# controller.net
KiCad netlist of a schematic drawn in EAGLE
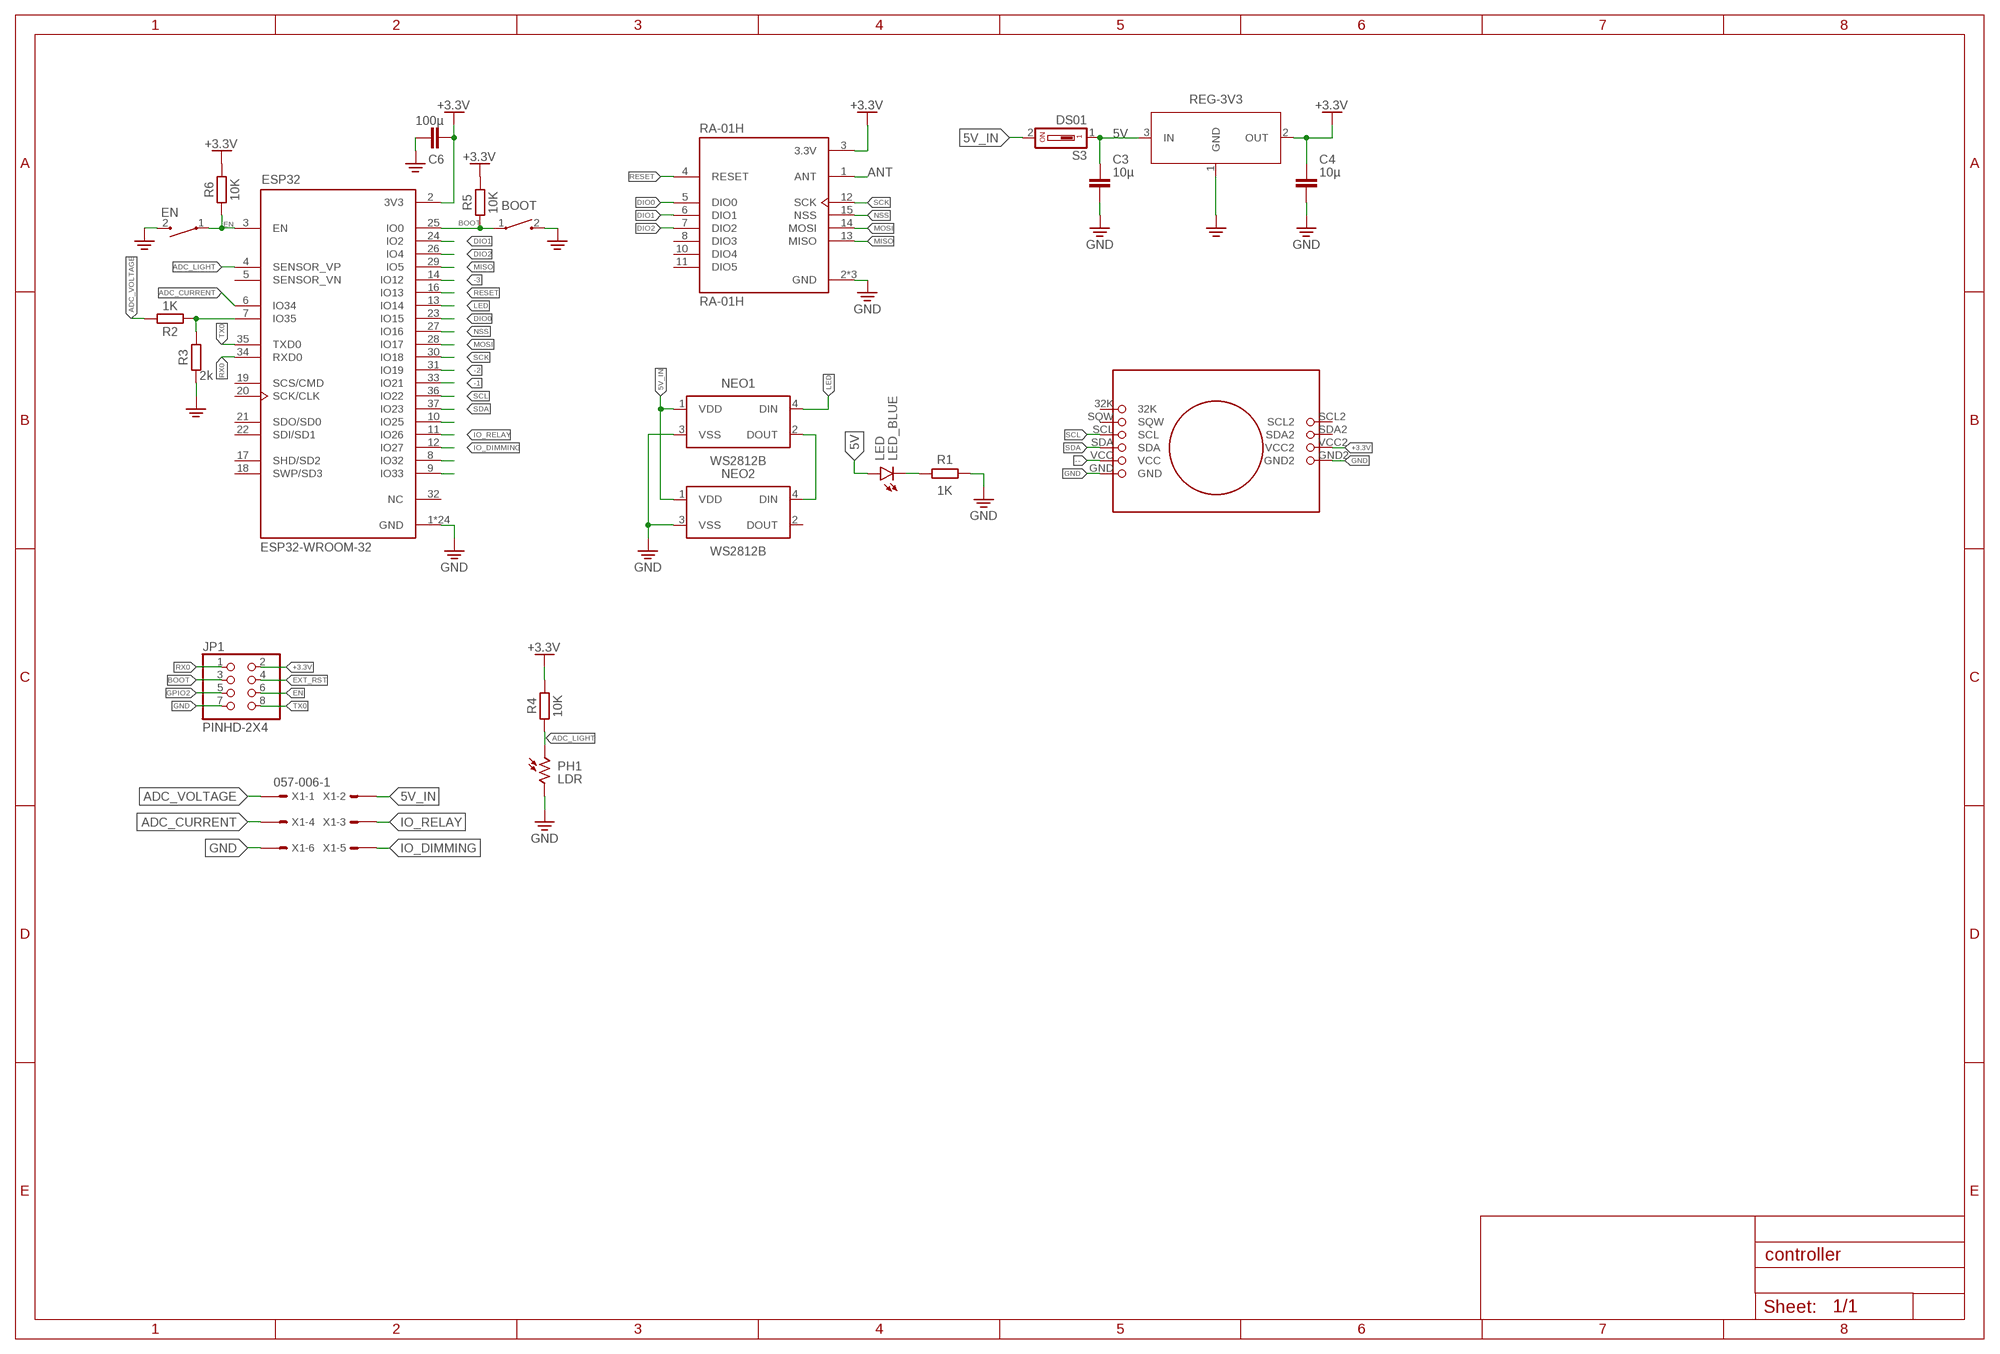
[diagram p0: schematic, sheet 1]

(export (version "E")
  (design (tool "Eeschema 10.0.6"))
  (components
    (comp (ref "BOOT")
      (value "SWITCH")
      (footprint "eagle-import:SW_1437566-3")
      (fields (field (name "MANUFACTURER") "TE CONNECTIVITY"))
      (libsource (lib "eagle-import") (part "SWITCH"))
    )
    (comp (ref "C3")
      (value "10µ")
      (footprint "eagle-import:CAPC2012X110")
      (libsource (lib "eagle-import") (part "CCHIP-0805(2012-METRIC)_"))
    )
    (comp (ref "C4")
      (value "10µ")
      (footprint "eagle-import:CAPC2012X110")
      (libsource (lib "eagle-import") (part "CCHIP-0805(2012-METRIC)_"))
    )
    (comp (ref "C6")
      (value "100µ")
      (footprint "eagle-import:CAPM6032X280")
      (libsource (lib "eagle-import") (part "CTANTALUM-2412(6032-METRIC)_"))
    )
    (comp (ref "EN")
      (value "SWITCH")
      (footprint "eagle-import:SW_1437566-3")
      (fields (field (name "MANUFACTURER") "TE CONNECTIVITY"))
      (libsource (lib "eagle-import") (part "SWITCH"))
    )
    (comp (ref "ESP32")
      (value "ESP32-WROOM-32")
      (footprint "eagle-import:MODULE_ESP32-WROOM-32")
      (fields (field (name "MANUFACTURER") "Espressif Systems"))
      (libsource (lib "eagle-import") (part "ESP32-WROOM-32"))
    )
    (comp (ref "JP1")
      (value "PINHD-2X4")
      (footprint "eagle-import:2X04")
      (libsource (lib "eagle-import") (part "PINHD-2X4"))
    )
    (comp (ref "LED")
      (value "LED_BLUE")
      (footprint "eagle-import:LEDC2012X110N_FLAT-B")
      (libsource (lib "eagle-import") (part "CHIP-FLAT-B_0805"))
    )
    (comp (ref "NEO1")
      (value "WS2812B")
      (footprint "eagle-import:WS2812B")
      (fields (field (name "MANUFACTURER") "Worldsemi"))
      (libsource (lib "eagle-import") (part "WS2812B"))
    )
    (comp (ref "NEO2")
      (value "WS2812B")
      (footprint "eagle-import:WS2812B")
      (fields (field (name "MANUFACTURER") "Worldsemi"))
      (libsource (lib "eagle-import") (part "WS2812B"))
    )
    (comp (ref "PH1")
      (value "LDR")
      (footprint "eagle-import:T0-46-A10XX")
      (libsource (lib "eagle-import") (part "A1050_09"))
    )
    (comp (ref "R1")
      (value "1K")
      (footprint "eagle-import:RESC2012X65")
      (libsource (lib "eagle-import") (part "RCHIP-0805(2012-METRIC)_"))
    )
    (comp (ref "R2")
      (value "1K")
      (footprint "eagle-import:RESC2012X65")
      (libsource (lib "eagle-import") (part "RCHIP-0805(2012-METRIC)_"))
    )
    (comp (ref "R3")
      (value "2k")
      (footprint "eagle-import:RESC2012X65")
      (libsource (lib "eagle-import") (part "RCHIP-0805(2012-METRIC)_"))
    )
    (comp (ref "R4")
      (value "10K")
      (footprint "eagle-import:RESC1608X60")
      (libsource (lib "eagle-import") (part "RCHIP-0603(1608-METRIC)_"))
    )
    (comp (ref "R5")
      (value "10K")
      (footprint "eagle-import:RESC2012X65")
      (libsource (lib "eagle-import") (part "RCHIP-0805(2012-METRIC)_"))
    )
    (comp (ref "R6")
      (value "10K")
      (footprint "eagle-import:RESC2012X65")
      (libsource (lib "eagle-import") (part "RCHIP-0805(2012-METRIC)_"))
    )
    (comp (ref "RA-01H")
      (value "RA-01H")
      (footprint "eagle-import:RA-01H")
      (fields (field (name "MANUFACTURER") "AI-Thinker"))
      (libsource (lib "eagle-import") (part "RA-01H"))
    )
    (comp (ref "REG-3V3")
      (value "NCP1117ST33T3G")
      (footprint "eagle-import:SOT230P700X170-4")
      (fields (field (name "MANUFACTURER") "ON Semiconductor"))
      (libsource (lib "eagle-import") (part "NCP1117ST33T3GSOT-223"))
    )
    (comp (ref "S3")
      (value "DS01")
      (footprint "eagle-import:DS-01")
      (libsource (lib "eagle-import") (part "DS01"))
    )
    (comp (ref "U$1")
      (value "DS3231_MODULE")
      (footprint "eagle-import:DS3231_MODULE")
      (libsource (lib "eagle-import") (part "DS3231_MODULE"))
    )
    (comp (ref "X1")
      (value "057-006-1")
      (footprint "eagle-import:057-006-1")
      (libsource (lib "eagle-import") (part "057-006-1"))
    )
  )
  (nets
    (net (code "1") (name "+3.3V") (class "Default")
      (node (ref "C4") (pin "1") (pinfunction "1_1") (pintype "passive"))
      (node (ref "C6") (pin "1") (pinfunction "1_1") (pintype "passive"))
      (node (ref "ESP32") (pin "2") (pinfunction "3V3_2") (pintype "power_in"))
      (node (ref "JP1") (pin "2") (pinfunction "2_2") (pintype "passive"))
      (node (ref "R4") (pin "2") (pinfunction "2_2") (pintype "passive"))
      (node (ref "R5") (pin "2") (pinfunction "2_2") (pintype "passive"))
      (node (ref "R6") (pin "2") (pinfunction "2_2") (pintype "passive"))
      (node (ref "RA-01H") (pin "3") (pinfunction "3.3V_3") (pintype "power_in"))
      (node (ref "REG-3V3") (pin "2") (pinfunction "OUT_2") (pintype "output"))
      (node (ref "U$1") (pin "VCC2") (pinfunction "VCC2_VCC2") (pintype "bidirectional"))
    )
    (net (code "2") (name "--") (class "Default")
      (node (ref "U$1") (pin "VCC") (pinfunction "VCC_VCC") (pintype "bidirectional"))
    )
    (net (code "3") (name "-1") (class "Default")
      (node (ref "ESP32") (pin "33") (pinfunction "IO21_33") (pintype "bidirectional"))
    )
    (net (code "4") (name "-2") (class "Default")
      (node (ref "ESP32") (pin "31") (pinfunction "IO19_31") (pintype "bidirectional"))
    )
    (net (code "5") (name "-3") (class "Default")
      (node (ref "ESP32") (pin "14") (pinfunction "IO12_14") (pintype "bidirectional"))
    )
    (net (code "6") (name "/ANT") (class "Default")
      (node (ref "RA-01H") (pin "1") (pinfunction "ANT_1") (pintype "bidirectional"))
    )
    (net (code "7") (name "5V") (class "Default")
      (node (ref "C3") (pin "1") (pinfunction "1_1") (pintype "passive"))
      (node (ref "LED") (pin "A") (pinfunction "A_A") (pintype "passive"))
      (node (ref "REG-3V3") (pin "3") (pinfunction "IN_3") (pintype "input"))
      (node (ref "S3") (pin "1") (pinfunction "1_1") (pintype "passive"))
    )
    (net (code "8") (name "5V_IN") (class "Default")
      (node (ref "NEO1") (pin "1") (pinfunction "VDD_1") (pintype "power_in"))
      (node (ref "NEO2") (pin "1") (pinfunction "VDD_1") (pintype "power_in"))
      (node (ref "S3") (pin "2") (pinfunction "2_2") (pintype "passive"))
      (node (ref "X1") (pin "2") (pinfunction "S_2") (pintype "passive"))
    )
    (net (code "9") (name "ADC_CURRENT") (class "Default")
      (node (ref "ESP32") (pin "6") (pinfunction "IO34_6") (pintype "input"))
      (node (ref "X1") (pin "4") (pinfunction "S_4") (pintype "passive"))
    )
    (net (code "10") (name "ADC_LIGHT") (class "Default")
      (node (ref "ESP32") (pin "4") (pinfunction "SENSOR_VP_4") (pintype "input"))
      (node (ref "PH1") (pin "1") (pinfunction "1_1") (pintype "passive"))
      (node (ref "R4") (pin "1") (pinfunction "1_1") (pintype "passive"))
    )
    (net (code "11") (name "ADC_VOLTAGE") (class "Default")
      (node (ref "R2") (pin "2") (pinfunction "2_2") (pintype "passive"))
      (node (ref "X1") (pin "1") (pinfunction "S_1") (pintype "passive"))
    )
    (net (code "12") (name "BOOT") (class "Default")
      (node (ref "BOOT") (pin "1") (pinfunction "1_1") (pintype "passive"))
      (node (ref "ESP32") (pin "25") (pinfunction "IO0_25") (pintype "bidirectional"))
      (node (ref "JP1") (pin "3") (pinfunction "3_3") (pintype "passive"))
      (node (ref "R5") (pin "1") (pinfunction "1_1") (pintype "passive"))
    )
    (net (code "13") (name "DIO0") (class "Default")
      (node (ref "ESP32") (pin "23") (pinfunction "IO15_23") (pintype "bidirectional"))
      (node (ref "RA-01H") (pin "5") (pinfunction "DIO0_5") (pintype "bidirectional"))
    )
    (net (code "14") (name "DIO1") (class "Default")
      (node (ref "ESP32") (pin "24") (pinfunction "IO2_24") (pintype "bidirectional"))
      (node (ref "RA-01H") (pin "6") (pinfunction "DIO1_6") (pintype "bidirectional"))
    )
    (net (code "15") (name "DIO2") (class "Default")
      (node (ref "ESP32") (pin "26") (pinfunction "IO4_26") (pintype "bidirectional"))
      (node (ref "RA-01H") (pin "7") (pinfunction "DIO2_7") (pintype "bidirectional"))
    )
    (net (code "16") (name "EN") (class "Default")
      (node (ref "EN") (pin "1") (pinfunction "1_1") (pintype "passive"))
      (node (ref "ESP32") (pin "3") (pinfunction "EN_3") (pintype "input"))
      (node (ref "JP1") (pin "6") (pinfunction "6_6") (pintype "passive"))
      (node (ref "R6") (pin "1") (pinfunction "1_1") (pintype "passive"))
    )
    (net (code "17") (name "EXT_RST") (class "Default")
      (node (ref "JP1") (pin "4") (pinfunction "4_4") (pintype "passive"))
    )
    (net (code "18") (name "GND") (class "Default")
      (node (ref "BOOT") (pin "2") (pinfunction "2_2") (pintype "passive"))
      (node (ref "C3") (pin "2") (pinfunction "2_2") (pintype "passive"))
      (node (ref "C4") (pin "2") (pinfunction "2_2") (pintype "passive"))
      (node (ref "C6") (pin "2") (pinfunction "2_2") (pintype "passive"))
      (node (ref "EN") (pin "2") (pinfunction "2_2") (pintype "passive"))
      (node (ref "ESP32") (pin "1") (pinfunction "GND_1") (pintype "power_in"))
      (node (ref "ESP32") (pin "15") (pinfunction "GND_15") (pintype "power_in"))
      (node (ref "ESP32") (pin "38") (pinfunction "GND_38") (pintype "power_in"))
      (node (ref "ESP32") (pin "39_1") (pinfunction "GND_39_1") (pintype "power_in"))
      (node (ref "ESP32") (pin "39_10") (pinfunction "GND_39_10") (pintype "power_in"))
      (node (ref "ESP32") (pin "39_11") (pinfunction "GND_39_11") (pintype "power_in"))
      (node (ref "ESP32") (pin "39_12") (pinfunction "GND_39_12") (pintype "power_in"))
      (node (ref "ESP32") (pin "39_13") (pinfunction "GND_39_13") (pintype "power_in"))
      (node (ref "ESP32") (pin "39_14") (pinfunction "GND_39_14") (pintype "power_in"))
      (node (ref "ESP32") (pin "39_15") (pinfunction "GND_39_15") (pintype "power_in"))
      (node (ref "ESP32") (pin "39_16") (pinfunction "GND_39_16") (pintype "power_in"))
      (node (ref "ESP32") (pin "39_17") (pinfunction "GND_39_17") (pintype "power_in"))
      (node (ref "ESP32") (pin "39_18") (pinfunction "GND_39_18") (pintype "power_in"))
      (node (ref "ESP32") (pin "39_19") (pinfunction "GND_39_19") (pintype "power_in"))
      (node (ref "ESP32") (pin "39_2") (pinfunction "GND_39_2") (pintype "power_in"))
      (node (ref "ESP32") (pin "39_20") (pinfunction "GND_39_20") (pintype "power_in"))
      (node (ref "ESP32") (pin "39_21") (pinfunction "GND_39_21") (pintype "power_in"))
      (node (ref "ESP32") (pin "39_3") (pinfunction "GND_39_3") (pintype "power_in"))
      (node (ref "ESP32") (pin "39_4") (pinfunction "GND_39_4") (pintype "power_in"))
      (node (ref "ESP32") (pin "39_5") (pinfunction "GND_39_5") (pintype "power_in"))
      (node (ref "ESP32") (pin "39_6") (pinfunction "GND_39_6") (pintype "power_in"))
      (node (ref "ESP32") (pin "39_7") (pinfunction "GND_39_7") (pintype "power_in"))
      (node (ref "ESP32") (pin "39_8") (pinfunction "GND_39_8") (pintype "power_in"))
      (node (ref "ESP32") (pin "39_9") (pinfunction "GND_39_9") (pintype "power_in"))
      (node (ref "JP1") (pin "7") (pinfunction "7_7") (pintype "passive"))
      (node (ref "NEO1") (pin "3") (pinfunction "VSS_3") (pintype "power_in"))
      (node (ref "NEO2") (pin "3") (pinfunction "VSS_3") (pintype "power_in"))
      (node (ref "PH1") (pin "2") (pinfunction "2_2") (pintype "passive"))
      (node (ref "R1") (pin "2") (pinfunction "2_2") (pintype "passive"))
      (node (ref "R3") (pin "1") (pinfunction "1_1") (pintype "passive"))
      (node (ref "RA-01H") (pin "16") (pinfunction "GND_16") (pintype "power_in"))
      (node (ref "RA-01H") (pin "2") (pinfunction "GND_2") (pintype "power_in"))
      (node (ref "RA-01H") (pin "9") (pinfunction "GND_9") (pintype "power_in"))
      (node (ref "REG-3V3") (pin "1") (pinfunction "GND_1") (pintype "passive"))
      (node (ref "U$1") (pin "GND") (pinfunction "GND_GND") (pintype "bidirectional"))
      (node (ref "U$1") (pin "GND2") (pinfunction "GND2_GND2") (pintype "bidirectional"))
      (node (ref "X1") (pin "6") (pinfunction "S_6") (pintype "passive"))
    )
    (net (code "19") (name "GPIO2") (class "Default")
      (node (ref "JP1") (pin "5") (pinfunction "5_5") (pintype "passive"))
    )
    (net (code "20") (name "IO_DIMMING") (class "Default")
      (node (ref "ESP32") (pin "12") (pinfunction "IO27_12") (pintype "bidirectional"))
      (node (ref "X1") (pin "5") (pinfunction "S_5") (pintype "passive"))
    )
    (net (code "21") (name "IO_RELAY") (class "Default")
      (node (ref "ESP32") (pin "11") (pinfunction "IO26_11") (pintype "bidirectional"))
      (node (ref "X1") (pin "3") (pinfunction "S_3") (pintype "passive"))
    )
    (net (code "22") (name "LED") (class "Default")
      (node (ref "ESP32") (pin "13") (pinfunction "IO14_13") (pintype "bidirectional"))
      (node (ref "NEO1") (pin "4") (pinfunction "DIN_4") (pintype "input"))
    )
    (net (code "23") (name "MISO") (class "Default")
      (node (ref "ESP32") (pin "29") (pinfunction "IO5_29") (pintype "bidirectional"))
      (node (ref "RA-01H") (pin "13") (pinfunction "MISO_13") (pintype "output"))
    )
    (net (code "24") (name "MOSI") (class "Default")
      (node (ref "ESP32") (pin "28") (pinfunction "IO17_28") (pintype "bidirectional"))
      (node (ref "RA-01H") (pin "14") (pinfunction "MOSI_14") (pintype "input"))
    )
    (net (code "25") (name "NSS") (class "Default")
      (node (ref "ESP32") (pin "27") (pinfunction "IO16_27") (pintype "bidirectional"))
      (node (ref "RA-01H") (pin "15") (pinfunction "NSS_15") (pintype "input"))
    )
    (net (code "26") (name "Net-(ESP32-IO35)") (class "Default")
      (node (ref "ESP32") (pin "7") (pinfunction "IO35_7") (pintype "input"))
      (node (ref "R2") (pin "1") (pinfunction "1_1") (pintype "passive"))
      (node (ref "R3") (pin "2") (pinfunction "2_2") (pintype "passive"))
    )
    (net (code "27") (name "Net-(LED-PadC)") (class "Default")
      (node (ref "LED") (pin "C") (pinfunction "C_C") (pintype "passive"))
      (node (ref "R1") (pin "1") (pinfunction "1_1") (pintype "passive"))
    )
    (net (code "28") (name "Net-(NEO1-DOUT)") (class "Default")
      (node (ref "NEO1") (pin "2") (pinfunction "DOUT_2") (pintype "output"))
      (node (ref "NEO2") (pin "4") (pinfunction "DIN_4") (pintype "input"))
    )
    (net (code "29") (name "RESET") (class "Default")
      (node (ref "ESP32") (pin "16") (pinfunction "IO13_16") (pintype "bidirectional"))
      (node (ref "RA-01H") (pin "4") (pinfunction "RESET_4") (pintype "input"))
    )
    (net (code "30") (name "RX0") (class "Default")
      (node (ref "ESP32") (pin "34") (pinfunction "RXD0_34") (pintype "bidirectional"))
      (node (ref "JP1") (pin "1") (pinfunction "1_1") (pintype "passive"))
    )
    (net (code "31") (name "SCK") (class "Default")
      (node (ref "ESP32") (pin "30") (pinfunction "IO18_30") (pintype "bidirectional"))
      (node (ref "RA-01H") (pin "12") (pinfunction "SCK_12") (pintype "input"))
    )
    (net (code "32") (name "SCL") (class "Default")
      (node (ref "ESP32") (pin "36") (pinfunction "IO22_36") (pintype "bidirectional"))
      (node (ref "U$1") (pin "SCL") (pinfunction "SCL_SCL") (pintype "bidirectional"))
    )
    (net (code "33") (name "SDA") (class "Default")
      (node (ref "ESP32") (pin "37") (pinfunction "IO23_37") (pintype "bidirectional"))
      (node (ref "U$1") (pin "SDA") (pinfunction "SDA_SDA") (pintype "bidirectional"))
    )
    (net (code "34") (name "TX0") (class "Default")
      (node (ref "ESP32") (pin "35") (pinfunction "TXD0_35") (pintype "bidirectional"))
      (node (ref "JP1") (pin "8") (pinfunction "8_8") (pintype "passive"))
    )
    (net (code "35") (name "unconnected-(ESP32-IO25-Pad10)") (class "Default")
      (node (ref "ESP32") (pin "10") (pinfunction "IO25_10") (pintype "bidirectional"))
    )
    (net (code "36") (name "unconnected-(ESP32-IO32-Pad8)") (class "Default")
      (node (ref "ESP32") (pin "8") (pinfunction "IO32_8") (pintype "bidirectional"))
    )
    (net (code "37") (name "unconnected-(ESP32-IO33-Pad9)") (class "Default")
      (node (ref "ESP32") (pin "9") (pinfunction "IO33_9") (pintype "bidirectional"))
    )
    (net (code "38") (name "unconnected-(ESP32-NC-Pad32)") (class "Default")
      (node (ref "ESP32") (pin "32") (pinfunction "NC_32") (pintype "no_connect"))
    )
    (net (code "39") (name "unconnected-(ESP32-SCK{slash}CLK-Pad20)") (class "Default")
      (node (ref "ESP32") (pin "20") (pinfunction "SCK/CLK_20") (pintype "bidirectional"))
    )
    (net (code "40") (name "unconnected-(ESP32-SCS{slash}CMD-Pad19)") (class "Default")
      (node (ref "ESP32") (pin "19") (pinfunction "SCS/CMD_19") (pintype "bidirectional"))
    )
    (net (code "41") (name "unconnected-(ESP32-SDI{slash}SD1-Pad22)") (class "Default")
      (node (ref "ESP32") (pin "22") (pinfunction "SDI/SD1_22") (pintype "bidirectional"))
    )
    (net (code "42") (name "unconnected-(ESP32-SDO{slash}SD0-Pad21)") (class "Default")
      (node (ref "ESP32") (pin "21") (pinfunction "SDO/SD0_21") (pintype "bidirectional"))
    )
    (net (code "43") (name "unconnected-(ESP32-SENSOR_VN-Pad5)") (class "Default")
      (node (ref "ESP32") (pin "5") (pinfunction "SENSOR_VN_5") (pintype "input"))
    )
    (net (code "44") (name "unconnected-(ESP32-SHD{slash}SD2-Pad17)") (class "Default")
      (node (ref "ESP32") (pin "17") (pinfunction "SHD/SD2_17") (pintype "bidirectional"))
    )
    (net (code "45") (name "unconnected-(ESP32-SWP{slash}SD3-Pad18)") (class "Default")
      (node (ref "ESP32") (pin "18") (pinfunction "SWP/SD3_18") (pintype "bidirectional"))
    )
    (net (code "46") (name "unconnected-(NEO2-DOUT-Pad2)") (class "Default")
      (node (ref "NEO2") (pin "2") (pinfunction "DOUT_2") (pintype "output"))
    )
    (net (code "47") (name "unconnected-(RA-01H-DIO3-Pad8)") (class "Default")
      (node (ref "RA-01H") (pin "8") (pinfunction "DIO3_8") (pintype "bidirectional"))
    )
    (net (code "48") (name "unconnected-(RA-01H-DIO4-Pad10)") (class "Default")
      (node (ref "RA-01H") (pin "10") (pinfunction "DIO4_10") (pintype "bidirectional"))
    )
    (net (code "49") (name "unconnected-(RA-01H-DIO5-Pad11)") (class "Default")
      (node (ref "RA-01H") (pin "11") (pinfunction "DIO5_11") (pintype "bidirectional"))
    )
    (net (code "50") (name "unconnected-(U$1-Pad32K)") (class "Default")
      (node (ref "U$1") (pin "32K") (pinfunction "32K_32K") (pintype "bidirectional"))
    )
    (net (code "51") (name "unconnected-(U$1-PadSCL2)") (class "Default")
      (node (ref "U$1") (pin "SCL2") (pinfunction "SCL2_SCL2") (pintype "bidirectional"))
    )
    (net (code "52") (name "unconnected-(U$1-PadSDA2)") (class "Default")
      (node (ref "U$1") (pin "SDA2") (pinfunction "SDA2_SDA2") (pintype "bidirectional"))
    )
    (net (code "53") (name "unconnected-(U$1-PadSQW)") (class "Default")
      (node (ref "U$1") (pin "SQW") (pinfunction "SQW_SQW") (pintype "bidirectional"))
    )
  )
)
